# Filter_Capacitors_-_Serial_Communication.net
KiCad netlist of a schematic drawn in Altium Designer
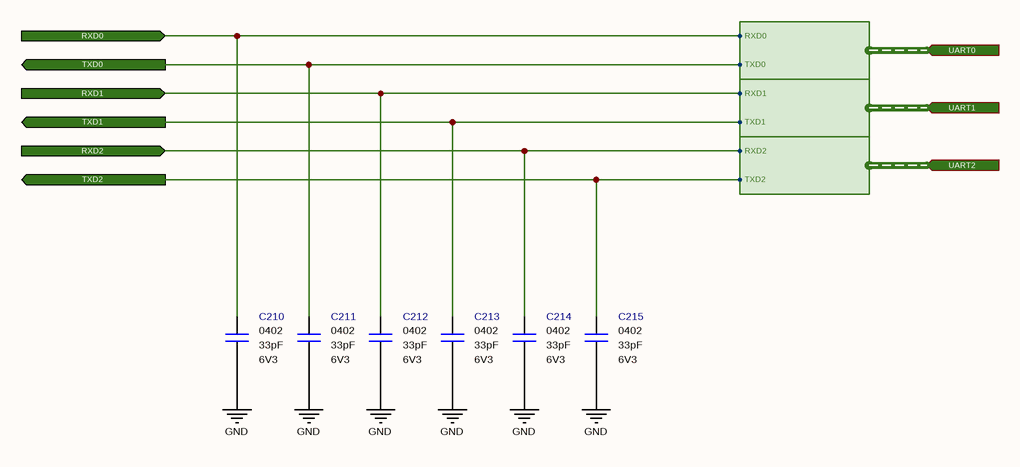
[diagram p0: Filter Capacitors - Serial Communication.SchDoc]

(export (version "E")
  (design (tool "Eeschema 10.0.6"))
  (components
    (comp (ref "C210")
      (value "33pF")
      (footprint "CAPACITOR_0402")
      (description "Capacitor - 33pF [0402] (Ceramic)")
      (fields
        (field (name "TOLERANCE") "10%")
        (field (name "CASE") "0402")
        (field (name "VOLTAGE") "6V3")
        (field (name "MANUFACTURER PART NUMBER") "C0402C330J9RACAUTO")
      )
      (libsource (lib "Ovoo_Library") (part "Capacitor - 33pF [0402-6V3]"))
    )
    (comp (ref "C211")
      (value "33pF")
      (footprint "CAPACITOR_0402")
      (description "Capacitor - 33pF [0402] (Ceramic)")
      (fields
        (field (name "TOLERANCE") "10%")
        (field (name "CASE") "0402")
        (field (name "VOLTAGE") "6V3")
        (field (name "MANUFACTURER PART NUMBER") "C0402C330J9RACAUTO")
      )
      (libsource (lib "Ovoo_Library") (part "Capacitor - 33pF [0402-6V3]"))
    )
    (comp (ref "C212")
      (value "33pF")
      (footprint "CAPACITOR_0402")
      (description "Capacitor - 33pF [0402] (Ceramic)")
      (fields
        (field (name "TOLERANCE") "10%")
        (field (name "CASE") "0402")
        (field (name "VOLTAGE") "6V3")
        (field (name "MANUFACTURER PART NUMBER") "C0402C330J9RACAUTO")
      )
      (libsource (lib "Ovoo_Library") (part "Capacitor - 33pF [0402-6V3]"))
    )
    (comp (ref "C213")
      (value "33pF")
      (footprint "CAPACITOR_0402")
      (description "Capacitor - 33pF [0402] (Ceramic)")
      (fields
        (field (name "TOLERANCE") "10%")
        (field (name "CASE") "0402")
        (field (name "VOLTAGE") "6V3")
        (field (name "MANUFACTURER PART NUMBER") "C0402C330J9RACAUTO")
      )
      (libsource (lib "Ovoo_Library") (part "Capacitor - 33pF [0402-6V3]"))
    )
    (comp (ref "C214")
      (value "33pF")
      (footprint "CAPACITOR_0402")
      (description "Capacitor - 33pF [0402] (Ceramic)")
      (fields
        (field (name "TOLERANCE") "10%")
        (field (name "CASE") "0402")
        (field (name "VOLTAGE") "6V3")
        (field (name "MANUFACTURER PART NUMBER") "C0402C330J9RACAUTO")
      )
      (libsource (lib "Ovoo_Library") (part "Capacitor - 33pF [0402-6V3]"))
    )
    (comp (ref "C215")
      (value "33pF")
      (footprint "CAPACITOR_0402")
      (description "Capacitor - 33pF [0402] (Ceramic)")
      (fields
        (field (name "TOLERANCE") "10%")
        (field (name "CASE") "0402")
        (field (name "VOLTAGE") "6V3")
        (field (name "MANUFACTURER PART NUMBER") "C0402C330J9RACAUTO")
      )
      (libsource (lib "Ovoo_Library") (part "Capacitor - 33pF [0402-6V3]"))
    )
  )
  (nets
    (net (code "4") (name "/RXD0") (class "Default")
      (node (ref "C210") (pin "2") (pinfunction "2_2") (pintype "passive"))
    )
    (net (code "5") (name "/RXD1") (class "Default")
      (node (ref "C212") (pin "2") (pinfunction "2_2") (pintype "passive"))
    )
    (net (code "6") (name "/RXD2") (class "Default")
      (node (ref "C214") (pin "2") (pinfunction "2_2") (pintype "passive"))
    )
    (net (code "7") (name "/TXD0") (class "Default")
      (node (ref "C211") (pin "2") (pinfunction "2_2") (pintype "passive"))
    )
    (net (code "8") (name "/TXD1") (class "Default")
      (node (ref "C213") (pin "2") (pinfunction "2_2") (pintype "passive"))
    )
    (net (code "9") (name "/TXD2") (class "Default")
      (node (ref "C215") (pin "2") (pinfunction "2_2") (pintype "passive"))
    )
    (net (code "13") (name "GND") (class "Default")
      (node (ref "C210") (pin "1") (pinfunction "1_1") (pintype "passive"))
      (node (ref "C211") (pin "1") (pinfunction "1_1") (pintype "passive"))
      (node (ref "C212") (pin "1") (pinfunction "1_1") (pintype "passive"))
      (node (ref "C213") (pin "1") (pinfunction "1_1") (pintype "passive"))
      (node (ref "C214") (pin "1") (pinfunction "1_1") (pintype "passive"))
      (node (ref "C215") (pin "1") (pinfunction "1_1") (pintype "passive"))
    )
  )
)
